# Diagrama_Final.net
KiCad netlist of a schematic drawn in Altium Designer
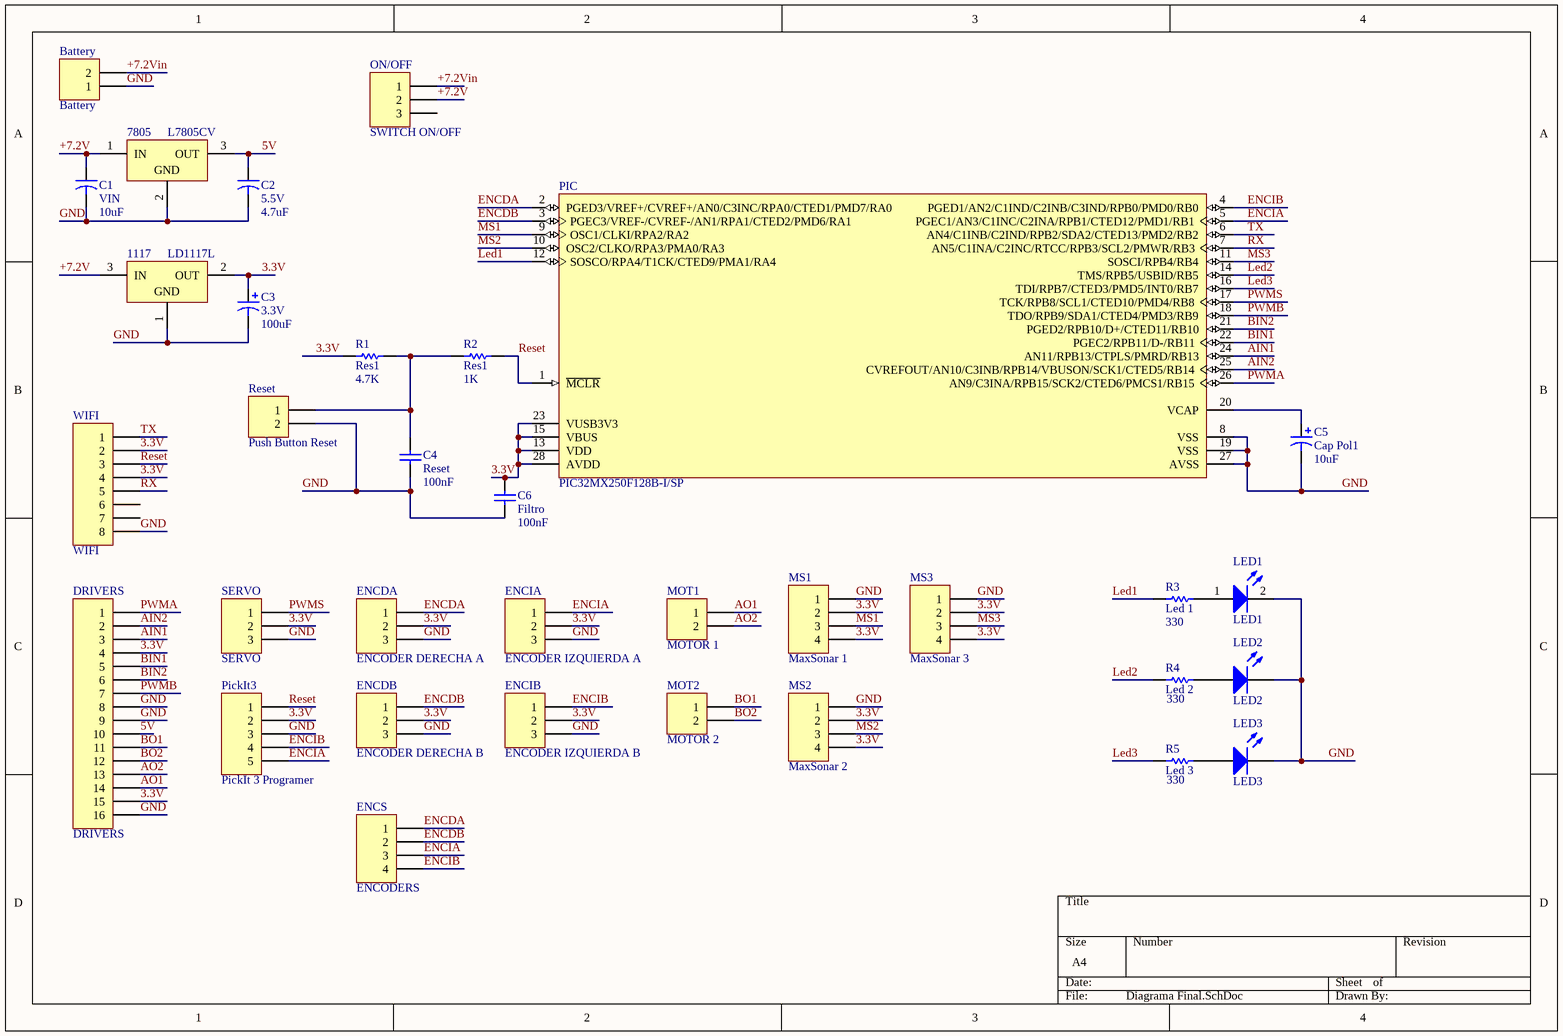
[diagram p0: Diagrama Final.SchDoc]

(export (version "E")
  (design (tool "Eeschema 10.0.6"))
  (components
    (comp (ref "1117")
      (value "LD1117L")
      (footprint "REG LD1117")
      (description "Precision 1A Regulator")
      (fields (field (name "PUBLISHER") "Altium Limited"))
      (libsource (lib "ST Power Mgt Voltage Regulator") (part "L7812ABV"))
    )
    (comp (ref "7805")
      (value "L7805CV")
      (footprint "REG 7805")
      (description "Precision 1A Regulator")
      (fields (field (name "PUBLISHER") "Altium Limited"))
      (libsource (lib "") (part "L7812ABV_1"))
    )
    (comp (ref "Battery")
      (value "Battery")
      (footprint "BATERIA")
      (description "Header, 2-Pin")
      (fields (field (name "PUBLISHER") "Altium Limited"))
      (libsource (lib "") (part "Header 2_1"))
    )
    (comp (ref "C1")
      (value "VIN")
      (footprint "Cap 10uF")
      (description "Capacitor")
      (fields (field (name "ALTIUM_VALUE") "10uF") (field (name "PUBLISHER") "Altium Limited"))
      (libsource (lib "Miscellaneous Devices") (part "Cap2"))
    )
    (comp (ref "C2")
      (value "5.5V")
      (footprint "Cap 4.7uF")
      (description "Capacitor")
      (fields (field (name "ALTIUM_VALUE") "4.7uF") (field (name "PUBLISHER") "Altium Limited"))
      (libsource (lib "Miscellaneous Devices") (part "Cap2"))
    )
    (comp (ref "C3")
      (value "3.3V")
      (footprint "Cap 100uF")
      (description "Polarized Capacitor (Radial)")
      (fields (field (name "ALTIUM_VALUE") "100uF") (field (name "PUBLISHER") "Altium Limited"))
      (libsource (lib "Miscellaneous Devices") (part "Cap Pol1"))
    )
    (comp (ref "C4")
      (value "Reset")
      (footprint "Cap 100nF")
      (description "Capacitor")
      (fields (field (name "ALTIUM_VALUE") "100nF") (field (name "PUBLISHER") "Altium Limited"))
      (libsource (lib "Miscellaneous Devices") (part "Cap"))
    )
    (comp (ref "C5")
      (value "Cap Pol1")
      (footprint "Cap 10uF")
      (description "Polarized Capacitor (Radial)")
      (fields (field (name "ALTIUM_VALUE") "10uF") (field (name "PUBLISHER") "Altium Limited"))
      (libsource (lib "Miscellaneous Devices") (part "Cap Pol1"))
    )
    (comp (ref "C6")
      (value "Filtro")
      (footprint "Cap 100nF")
      (description "Capacitor")
      (fields (field (name "ALTIUM_VALUE") "100nF") (field (name "PUBLISHER") "Altium Limited"))
      (libsource (lib "Miscellaneous Devices") (part "Cap"))
    )
    (comp (ref "DRIVERS")
      (value "DRIVERS")
      (footprint "Drivers")
      (description "Header, 16-Pin")
      (fields (field (name "PUBLISHER") "Altium Limited"))
      (libsource (lib "Miscellaneous Connectors") (part "Header 16"))
    )
    (comp (ref "ENCDA")
      (value "ENCODER DERECHA A")
      (footprint "ENCODER")
      (description "Header, 3-Pin")
      (fields (field (name "PUBLISHER") "Altium Limited"))
      (libsource (lib "Miscellaneous Connectors") (part "Header 3"))
    )
    (comp (ref "ENCDB")
      (value "ENCODER DERECHA B")
      (footprint "ENCODER")
      (description "Header, 3-Pin")
      (fields (field (name "PUBLISHER") "Altium Limited"))
      (libsource (lib "Miscellaneous Connectors") (part "Header 3"))
    )
    (comp (ref "ENCIA")
      (value "ENCODER IZQUIERDA A")
      (footprint "ENCODER")
      (description "Header, 3-Pin")
      (fields (field (name "PUBLISHER") "Altium Limited"))
      (libsource (lib "Miscellaneous Connectors") (part "Header 3"))
    )
    (comp (ref "ENCIB")
      (value "ENCODER IZQUIERDA B")
      (footprint "ENCODER")
      (description "Header, 3-Pin")
      (fields (field (name "PUBLISHER") "Altium Limited"))
      (libsource (lib "Miscellaneous Connectors") (part "Header 3"))
    )
    (comp (ref "ENCS")
      (value "ENCODERS")
      (footprint "PINES - 4")
      (description "Header, 4-Pin")
      (fields (field (name "PUBLISHER") "Altium Limited"))
      (libsource (lib "Miscellaneous Connectors") (part "Header 4"))
    )
    (comp (ref "LED1")
      (value "LED1")
      (footprint "LED")
      (description "Typical INFRARED GaAs LED")
      (fields (field (name "PUBLISHER") "Altium Limited"))
      (libsource (lib "") (part "LED0_1"))
    )
    (comp (ref "LED2")
      (value "LED2")
      (footprint "LED")
      (description "Typical INFRARED GaAs LED")
      (fields (field (name "PUBLISHER") "Altium Limited"))
      (libsource (lib "Miscellaneous Devices") (part "LED0"))
    )
    (comp (ref "LED3")
      (value "LED3")
      (footprint "LED")
      (description "Typical INFRARED GaAs LED")
      (fields (field (name "PUBLISHER") "Altium Limited"))
      (libsource (lib "Miscellaneous Devices") (part "LED0"))
    )
    (comp (ref "MOT1")
      (value "MOTOR 1")
      (footprint "MOTOR")
      (description "Header, 2-Pin")
      (fields (field (name "PUBLISHER") "Altium Limited"))
      (libsource (lib "Miscellaneous Connectors") (part "Header 2"))
    )
    (comp (ref "MOT2")
      (value "MOTOR 2")
      (footprint "MOTOR")
      (description "Header, 2-Pin")
      (fields (field (name "PUBLISHER") "Altium Limited"))
      (libsource (lib "Miscellaneous Connectors") (part "Header 2"))
    )
    (comp (ref "MS1")
      (value "MaxSonar 1")
      (footprint "MaxSonar")
      (description "Header, 4-Pin")
      (fields (field (name "PUBLISHER") "Altium Limited"))
      (libsource (lib "Miscellaneous Connectors") (part "Header 4"))
    )
    (comp (ref "MS2")
      (value "MaxSonar 2")
      (footprint "MaxSonar")
      (description "Header, 4-Pin")
      (fields (field (name "PUBLISHER") "Altium Limited"))
      (libsource (lib "Miscellaneous Connectors") (part "Header 4"))
    )
    (comp (ref "MS3")
      (value "MaxSonar 3")
      (footprint "MaxSonar")
      (description "Header, 4-Pin")
      (fields (field (name "PUBLISHER") "Altium Limited"))
      (libsource (lib "Miscellaneous Connectors") (part "Header 4"))
    )
    (comp (ref "ON/OFF")
      (value "SWITCH ON/OFF")
      (footprint "Switch ON/OFF")
      (description "Header, 3-Pin")
      (fields (field (name "PUBLISHER") "Altium Limited"))
      (libsource (lib "Miscellaneous Connectors") (part "Header 3"))
    )
    (comp (ref "PIC")
      (value "PIC32MX250F128B-I/SP")
      (footprint "Camita-28")
      (fields (field (name "MANUFACTURER") "Microchip"))
      (libsource (lib "Microchip PIC32MX") (part "PIC32MX250F128B-I/SP"))
    )
    (comp (ref "PickIt3")
      (value "PickIt 3 Programer")
      (footprint "PINES - 5")
      (description "Header, 5-Pin")
      (fields (field (name "PUBLISHER") "Altium Limited"))
      (libsource (lib "Miscellaneous Connectors") (part "Header 5"))
    )
    (comp (ref "R1")
      (value "Res1")
      (footprint "Resistor")
      (description "Resistor")
      (fields (field (name "ALTIUM_VALUE") "4.7K") (field (name "PUBLISHER") "Altium Limited"))
      (libsource (lib "Miscellaneous Devices") (part "Res1"))
    )
    (comp (ref "R2")
      (value "Res1")
      (footprint "Resistor")
      (description "Resistor")
      (fields (field (name "ALTIUM_VALUE") "1K") (field (name "PUBLISHER") "Altium Limited"))
      (libsource (lib "Miscellaneous Devices") (part "Res1"))
    )
    (comp (ref "R3")
      (value "Led 1")
      (footprint "Resistor")
      (description "Resistor")
      (fields (field (name "ALTIUM_VALUE") "330") (field (name "PUBLISHER") "Altium Limited"))
      (libsource (lib "Miscellaneous Devices") (part "Res1"))
    )
    (comp (ref "R4")
      (value "Led 2")
      (footprint "Resistor")
      (description "Resistor")
      (fields (field (name "ALTIUM_VALUE") "330") (field (name "PUBLISHER") "Altium Limited"))
      (libsource (lib "Miscellaneous Devices") (part "Res1"))
    )
    (comp (ref "R5")
      (value "Led 3")
      (footprint "Resistor")
      (description "Resistor")
      (fields (field (name "ALTIUM_VALUE") "330") (field (name "PUBLISHER") "Altium Limited"))
      (libsource (lib "Miscellaneous Devices") (part "Res1"))
    )
    (comp (ref "Reset")
      (value "Push Button Reset")
      (footprint "Push Button")
      (description "Header, 2-Pin")
      (fields (field (name "PUBLISHER") "Altium Limited"))
      (libsource (lib "Miscellaneous Connectors") (part "Header 2"))
    )
    (comp (ref "SERVO")
      (value "SERVO")
      (footprint "SERVO")
      (description "Header, 3-Pin")
      (fields (field (name "PUBLISHER") "Altium Limited"))
      (libsource (lib "Miscellaneous Connectors") (part "Header 3"))
    )
    (comp (ref "WIFI")
      (value "WIFI")
      (footprint "WIFI")
      (description "Header, 8-Pin")
      (fields (field (name "PUBLISHER") "Altium Limited"))
      (libsource (lib "Miscellaneous Connectors") (part "Header 8"))
    )
  )
  (nets
    (net (code "1") (name "/+7.2V") (class "Default")
      (node (ref "1117") (pin "3") (pinfunction "IN_3") (pintype "power_in"))
      (node (ref "7805") (pin "1") (pinfunction "IN_1") (pintype "power_in"))
      (node (ref "C1") (pin "1") (pinfunction "1_1") (pintype "passive"))
      (node (ref "ON/OFF") (pin "2") (pinfunction "2_2") (pintype "passive"))
    )
    (net (code "2") (name "/+7.2Vin") (class "Default")
      (node (ref "Battery") (pin "2") (pinfunction "2_2") (pintype "passive"))
      (node (ref "ON/OFF") (pin "1") (pinfunction "1_1") (pintype "passive"))
    )
    (net (code "3") (name "/3.3V") (class "Default")
      (node (ref "1117") (pin "2") (pinfunction "OUT_2") (pintype "power_in"))
      (node (ref "C3") (pin "1") (pinfunction "1_1") (pintype "passive"))
      (node (ref "C6") (pin "1") (pinfunction "1_1") (pintype "passive"))
      (node (ref "DRIVERS") (pin "15") (pinfunction "15_15") (pintype "passive"))
      (node (ref "DRIVERS") (pin "4") (pinfunction "4_4") (pintype "passive"))
      (node (ref "ENCDA") (pin "2") (pinfunction "2_2") (pintype "passive"))
      (node (ref "ENCDB") (pin "2") (pinfunction "2_2") (pintype "passive"))
      (node (ref "ENCIA") (pin "2") (pinfunction "2_2") (pintype "passive"))
      (node (ref "ENCIB") (pin "2") (pinfunction "2_2") (pintype "passive"))
      (node (ref "MS1") (pin "2") (pinfunction "2_2") (pintype "passive"))
      (node (ref "MS1") (pin "4") (pinfunction "4_4") (pintype "passive"))
      (node (ref "MS2") (pin "2") (pinfunction "2_2") (pintype "passive"))
      (node (ref "MS2") (pin "4") (pinfunction "4_4") (pintype "passive"))
      (node (ref "MS3") (pin "2") (pinfunction "2_2") (pintype "passive"))
      (node (ref "MS3") (pin "4") (pinfunction "4_4") (pintype "passive"))
      (node (ref "PIC") (pin "13") (pinfunction "VDD_13") (pintype "power_in"))
      (node (ref "PIC") (pin "15") (pinfunction "VBUS_15") (pintype "power_in"))
      (node (ref "PIC") (pin "23") (pinfunction "VUSB3V3_23") (pintype "power_in"))
      (node (ref "PIC") (pin "28") (pinfunction "AVDD_28") (pintype "power_in"))
      (node (ref "PickIt3") (pin "2") (pinfunction "2_2") (pintype "passive"))
      (node (ref "R1") (pin "2") (pinfunction "2_2") (pintype "passive"))
      (node (ref "SERVO") (pin "2") (pinfunction "2_2") (pintype "passive"))
      (node (ref "WIFI") (pin "2") (pinfunction "2_2") (pintype "passive"))
      (node (ref "WIFI") (pin "4") (pinfunction "4_4") (pintype "passive"))
    )
    (net (code "4") (name "/5V") (class "Default")
      (node (ref "7805") (pin "3") (pinfunction "OUT_3") (pintype "power_in"))
      (node (ref "C2") (pin "1") (pinfunction "1_1") (pintype "passive"))
      (node (ref "DRIVERS") (pin "10") (pinfunction "10_10") (pintype "passive"))
    )
    (net (code "5") (name "/AIN1") (class "Default")
      (node (ref "DRIVERS") (pin "3") (pinfunction "3_3") (pintype "passive"))
      (node (ref "PIC") (pin "24") (pinfunction "AN11/RPB13/CTPLS/PMRD/RB13_24") (pintype "bidirectional"))
    )
    (net (code "6") (name "/AIN2") (class "Default")
      (node (ref "DRIVERS") (pin "2") (pinfunction "2_2") (pintype "passive"))
      (node (ref "PIC") (pin "25") (pinfunction "CVREFOUT/AN10/C3INB/RPB14/VBUSON/SCK1/CTED5/RB14_25") (pintype "bidirectional"))
    )
    (net (code "7") (name "/AO1") (class "Default")
      (node (ref "DRIVERS") (pin "14") (pinfunction "14_14") (pintype "passive"))
      (node (ref "MOT1") (pin "1") (pinfunction "1_1") (pintype "passive"))
    )
    (net (code "8") (name "/AO2") (class "Default")
      (node (ref "DRIVERS") (pin "13") (pinfunction "13_13") (pintype "passive"))
      (node (ref "MOT1") (pin "2") (pinfunction "2_2") (pintype "passive"))
    )
    (net (code "9") (name "/BIN1") (class "Default")
      (node (ref "DRIVERS") (pin "5") (pinfunction "5_5") (pintype "passive"))
      (node (ref "PIC") (pin "22") (pinfunction "PGEC2/RPB11/D-/RB11_22") (pintype "bidirectional"))
    )
    (net (code "10") (name "/BIN2") (class "Default")
      (node (ref "DRIVERS") (pin "6") (pinfunction "6_6") (pintype "passive"))
      (node (ref "PIC") (pin "21") (pinfunction "PGED2/RPB10/D+/CTED11/RB10_21") (pintype "bidirectional"))
    )
    (net (code "11") (name "/BO1") (class "Default")
      (node (ref "DRIVERS") (pin "11") (pinfunction "11_11") (pintype "passive"))
      (node (ref "MOT2") (pin "1") (pinfunction "1_1") (pintype "passive"))
    )
    (net (code "12") (name "/BO2") (class "Default")
      (node (ref "DRIVERS") (pin "12") (pinfunction "12_12") (pintype "passive"))
      (node (ref "MOT2") (pin "2") (pinfunction "2_2") (pintype "passive"))
    )
    (net (code "13") (name "/ENCDA") (class "Default")
      (node (ref "ENCDA") (pin "1") (pinfunction "1_1") (pintype "passive"))
      (node (ref "ENCS") (pin "1") (pinfunction "1_1") (pintype "passive"))
      (node (ref "PIC") (pin "2") (pinfunction "PGED3/VREF+/CVREF+/AN0/C3INC/RPA0/CTED1/PMD7/RA0_2") (pintype "bidirectional"))
    )
    (net (code "14") (name "/ENCDB") (class "Default")
      (node (ref "ENCDB") (pin "1") (pinfunction "1_1") (pintype "passive"))
      (node (ref "ENCS") (pin "2") (pinfunction "2_2") (pintype "passive"))
      (node (ref "PIC") (pin "3") (pinfunction "PGEC3/VREF-/CVREF-/AN1/RPA1/CTED2/PMD6/RA1_3") (pintype "bidirectional"))
    )
    (net (code "15") (name "/ENCIA") (class "Default")
      (node (ref "ENCIA") (pin "1") (pinfunction "1_1") (pintype "passive"))
      (node (ref "ENCS") (pin "3") (pinfunction "3_3") (pintype "passive"))
      (node (ref "PIC") (pin "5") (pinfunction "PGEC1/AN3/C1INC/C2INA/RPB1/CTED12/PMD1/RB1_5") (pintype "bidirectional"))
      (node (ref "PickIt3") (pin "5") (pinfunction "5_5") (pintype "passive"))
    )
    (net (code "16") (name "/ENCIB") (class "Default")
      (node (ref "ENCIB") (pin "1") (pinfunction "1_1") (pintype "passive"))
      (node (ref "ENCS") (pin "4") (pinfunction "4_4") (pintype "passive"))
      (node (ref "PIC") (pin "4") (pinfunction "PGED1/AN2/C1IND/C2INB/C3IND/RPB0/PMD0/RB0_4") (pintype "bidirectional"))
      (node (ref "PickIt3") (pin "4") (pinfunction "4_4") (pintype "passive"))
    )
    (net (code "17") (name "/GND") (class "Default")
      (node (ref "1117") (pin "1") (pinfunction "GND_1") (pintype "power_in"))
      (node (ref "7805") (pin "2") (pinfunction "GND_2") (pintype "power_in"))
      (node (ref "Battery") (pin "1") (pinfunction "1_1") (pintype "passive"))
      (node (ref "C1") (pin "2") (pinfunction "2_2") (pintype "passive"))
      (node (ref "C2") (pin "2") (pinfunction "2_2") (pintype "passive"))
      (node (ref "C3") (pin "2") (pinfunction "2_2") (pintype "passive"))
      (node (ref "C4") (pin "2") (pinfunction "2_2") (pintype "passive"))
      (node (ref "C5") (pin "2") (pinfunction "2_2") (pintype "passive"))
      (node (ref "C6") (pin "2") (pinfunction "2_2") (pintype "passive"))
      (node (ref "DRIVERS") (pin "16") (pinfunction "16_16") (pintype "passive"))
      (node (ref "DRIVERS") (pin "8") (pinfunction "8_8") (pintype "passive"))
      (node (ref "DRIVERS") (pin "9") (pinfunction "9_9") (pintype "passive"))
      (node (ref "ENCDA") (pin "3") (pinfunction "3_3") (pintype "passive"))
      (node (ref "ENCDB") (pin "3") (pinfunction "3_3") (pintype "passive"))
      (node (ref "ENCIA") (pin "3") (pinfunction "3_3") (pintype "passive"))
      (node (ref "ENCIB") (pin "3") (pinfunction "3_3") (pintype "passive"))
      (node (ref "LED1") (pin "2") (pinfunction "K_2") (pintype "passive"))
      (node (ref "LED2") (pin "2") (pinfunction "K_2") (pintype "passive"))
      (node (ref "LED3") (pin "2") (pinfunction "K_2") (pintype "passive"))
      (node (ref "MS1") (pin "1") (pinfunction "1_1") (pintype "passive"))
      (node (ref "MS2") (pin "1") (pinfunction "1_1") (pintype "passive"))
      (node (ref "MS3") (pin "1") (pinfunction "1_1") (pintype "passive"))
      (node (ref "PIC") (pin "19") (pinfunction "VSS_19") (pintype "power_in"))
      (node (ref "PIC") (pin "27") (pinfunction "AVSS_27") (pintype "power_in"))
      (node (ref "PIC") (pin "8") (pinfunction "VSS_8") (pintype "power_in"))
      (node (ref "PickIt3") (pin "3") (pinfunction "3_3") (pintype "passive"))
      (node (ref "Reset") (pin "2") (pinfunction "2_2") (pintype "passive"))
      (node (ref "SERVO") (pin "3") (pinfunction "3_3") (pintype "passive"))
      (node (ref "WIFI") (pin "8") (pinfunction "8_8") (pintype "passive"))
    )
    (net (code "18") (name "/Led1") (class "Default")
      (node (ref "PIC") (pin "12") (pinfunction "SOSCO/RPA4/T1CK/CTED9/PMA1/RA4_12") (pintype "bidirectional"))
      (node (ref "R3") (pin "2") (pinfunction "2_2") (pintype "passive"))
    )
    (net (code "19") (name "/Led2") (class "Default")
      (node (ref "PIC") (pin "14") (pinfunction "TMS/RPB5/USBID/RB5_14") (pintype "bidirectional"))
      (node (ref "R4") (pin "2") (pinfunction "2_2") (pintype "passive"))
    )
    (net (code "20") (name "/Led3") (class "Default")
      (node (ref "PIC") (pin "16") (pinfunction "TDI/RPB7/CTED3/PMD5/INT0/RB7_16") (pintype "bidirectional"))
      (node (ref "R5") (pin "2") (pinfunction "2_2") (pintype "passive"))
    )
    (net (code "21") (name "/MS1") (class "Default")
      (node (ref "MS1") (pin "3") (pinfunction "3_3") (pintype "passive"))
      (node (ref "PIC") (pin "9") (pinfunction "OSC1/CLKI/RPA2/RA2_9") (pintype "bidirectional"))
    )
    (net (code "22") (name "/MS2") (class "Default")
      (node (ref "MS2") (pin "3") (pinfunction "3_3") (pintype "passive"))
      (node (ref "PIC") (pin "10") (pinfunction "OSC2/CLKO/RPA3/PMA0/RA3_10") (pintype "bidirectional"))
    )
    (net (code "23") (name "/MS3") (class "Default")
      (node (ref "MS3") (pin "3") (pinfunction "3_3") (pintype "passive"))
      (node (ref "PIC") (pin "11") (pinfunction "SOSCI/RPB4/RB4_11") (pintype "bidirectional"))
    )
    (net (code "24") (name "/PWMA") (class "Default")
      (node (ref "DRIVERS") (pin "1") (pinfunction "1_1") (pintype "passive"))
      (node (ref "PIC") (pin "26") (pinfunction "AN9/C3INA/RPB15/SCK2/CTED6/PMCS1/RB15_26") (pintype "bidirectional"))
    )
    (net (code "25") (name "/PWMB") (class "Default")
      (node (ref "DRIVERS") (pin "7") (pinfunction "7_7") (pintype "passive"))
      (node (ref "PIC") (pin "18") (pinfunction "TDO/RPB9/SDA1/CTED4/PMD3/RB9_18") (pintype "bidirectional"))
    )
    (net (code "26") (name "/PWMS") (class "Default")
      (node (ref "PIC") (pin "17") (pinfunction "TCK/RPB8/SCL1/CTED10/PMD4/RB8_17") (pintype "bidirectional"))
      (node (ref "SERVO") (pin "1") (pinfunction "1_1") (pintype "passive"))
    )
    (net (code "27") (name "/RX") (class "Default")
      (node (ref "PIC") (pin "7") (pinfunction "AN5/C1INA/C2INC/RTCC/RPB3/SCL2/PMWR/RB3_7") (pintype "bidirectional"))
      (node (ref "WIFI") (pin "5") (pinfunction "5_5") (pintype "passive"))
    )
    (net (code "28") (name "/Reset") (class "Default")
      (node (ref "PIC") (pin "1") (pinfunction "~{MCLR}_1") (pintype "input"))
      (node (ref "PickIt3") (pin "1") (pinfunction "1_1") (pintype "passive"))
      (node (ref "R2") (pin "1") (pinfunction "1_1") (pintype "passive"))
      (node (ref "WIFI") (pin "3") (pinfunction "3_3") (pintype "passive"))
    )
    (net (code "29") (name "/TX") (class "Default")
      (node (ref "PIC") (pin "6") (pinfunction "AN4/C1INB/C2IND/RPB2/SDA2/CTED13/PMD2/RB2_6") (pintype "bidirectional"))
      (node (ref "WIFI") (pin "1") (pinfunction "1_1") (pintype "passive"))
    )
    (net (code "30") (name "Net-(C4-Pad1)") (class "Default")
      (node (ref "C4") (pin "1") (pinfunction "1_1") (pintype "passive"))
      (node (ref "R1") (pin "1") (pinfunction "1_1") (pintype "passive"))
      (node (ref "R2") (pin "2") (pinfunction "2_2") (pintype "passive"))
      (node (ref "Reset") (pin "1") (pinfunction "1_1") (pintype "passive"))
    )
    (net (code "31") (name "Net-(LED1-A)") (class "Default")
      (node (ref "LED1") (pin "1") (pinfunction "A_1") (pintype "passive"))
      (node (ref "R3") (pin "1") (pinfunction "1_1") (pintype "passive"))
    )
    (net (code "32") (name "Net-(LED2-A)") (class "Default")
      (node (ref "LED2") (pin "1") (pinfunction "A_1") (pintype "passive"))
      (node (ref "R4") (pin "1") (pinfunction "1_1") (pintype "passive"))
    )
    (net (code "33") (name "Net-(LED3-A)") (class "Default")
      (node (ref "LED3") (pin "1") (pinfunction "A_1") (pintype "passive"))
      (node (ref "R5") (pin "1") (pinfunction "1_1") (pintype "passive"))
    )
    (net (code "34") (name "Net-(PIC-VCAP)") (class "Default")
      (node (ref "C5") (pin "1") (pinfunction "1_1") (pintype "passive"))
      (node (ref "PIC") (pin "20") (pinfunction "VCAP_20") (pintype "passive"))
    )
    (net (code "35") (name "unconnected-(ON/OFF-Pad3)") (class "Default")
      (node (ref "ON/OFF") (pin "3") (pinfunction "3_3") (pintype "passive"))
    )
    (net (code "36") (name "unconnected-(WIFI-Pad6)") (class "Default")
      (node (ref "WIFI") (pin "6") (pinfunction "6_6") (pintype "passive"))
    )
    (net (code "37") (name "unconnected-(WIFI-Pad7)") (class "Default")
      (node (ref "WIFI") (pin "7") (pinfunction "7_7") (pintype "passive"))
    )
  )
)
